# PCB_dol.net
KiCad netlist of a schematic drawn in EAGLE
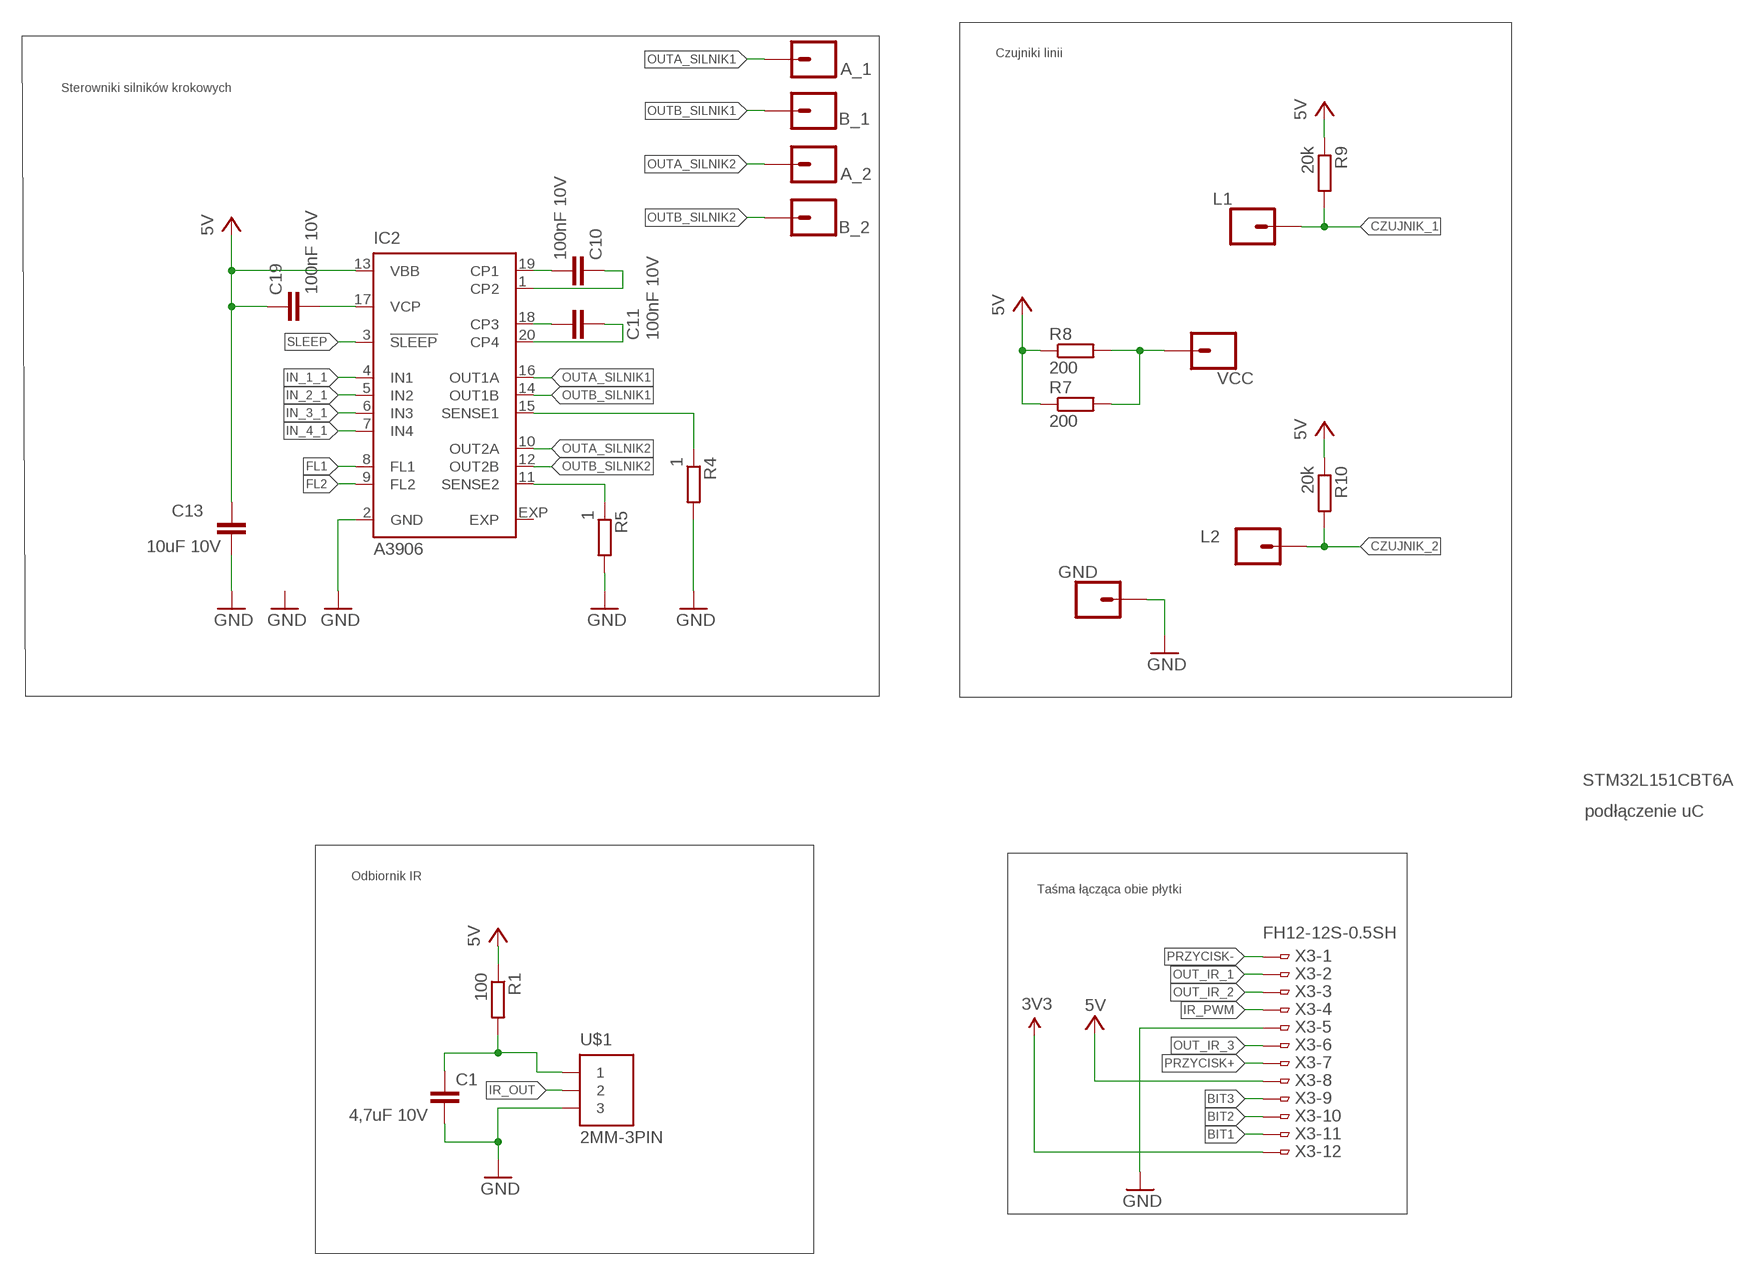
[diagram p0: schematic, sheet 1, part 1 of 2]
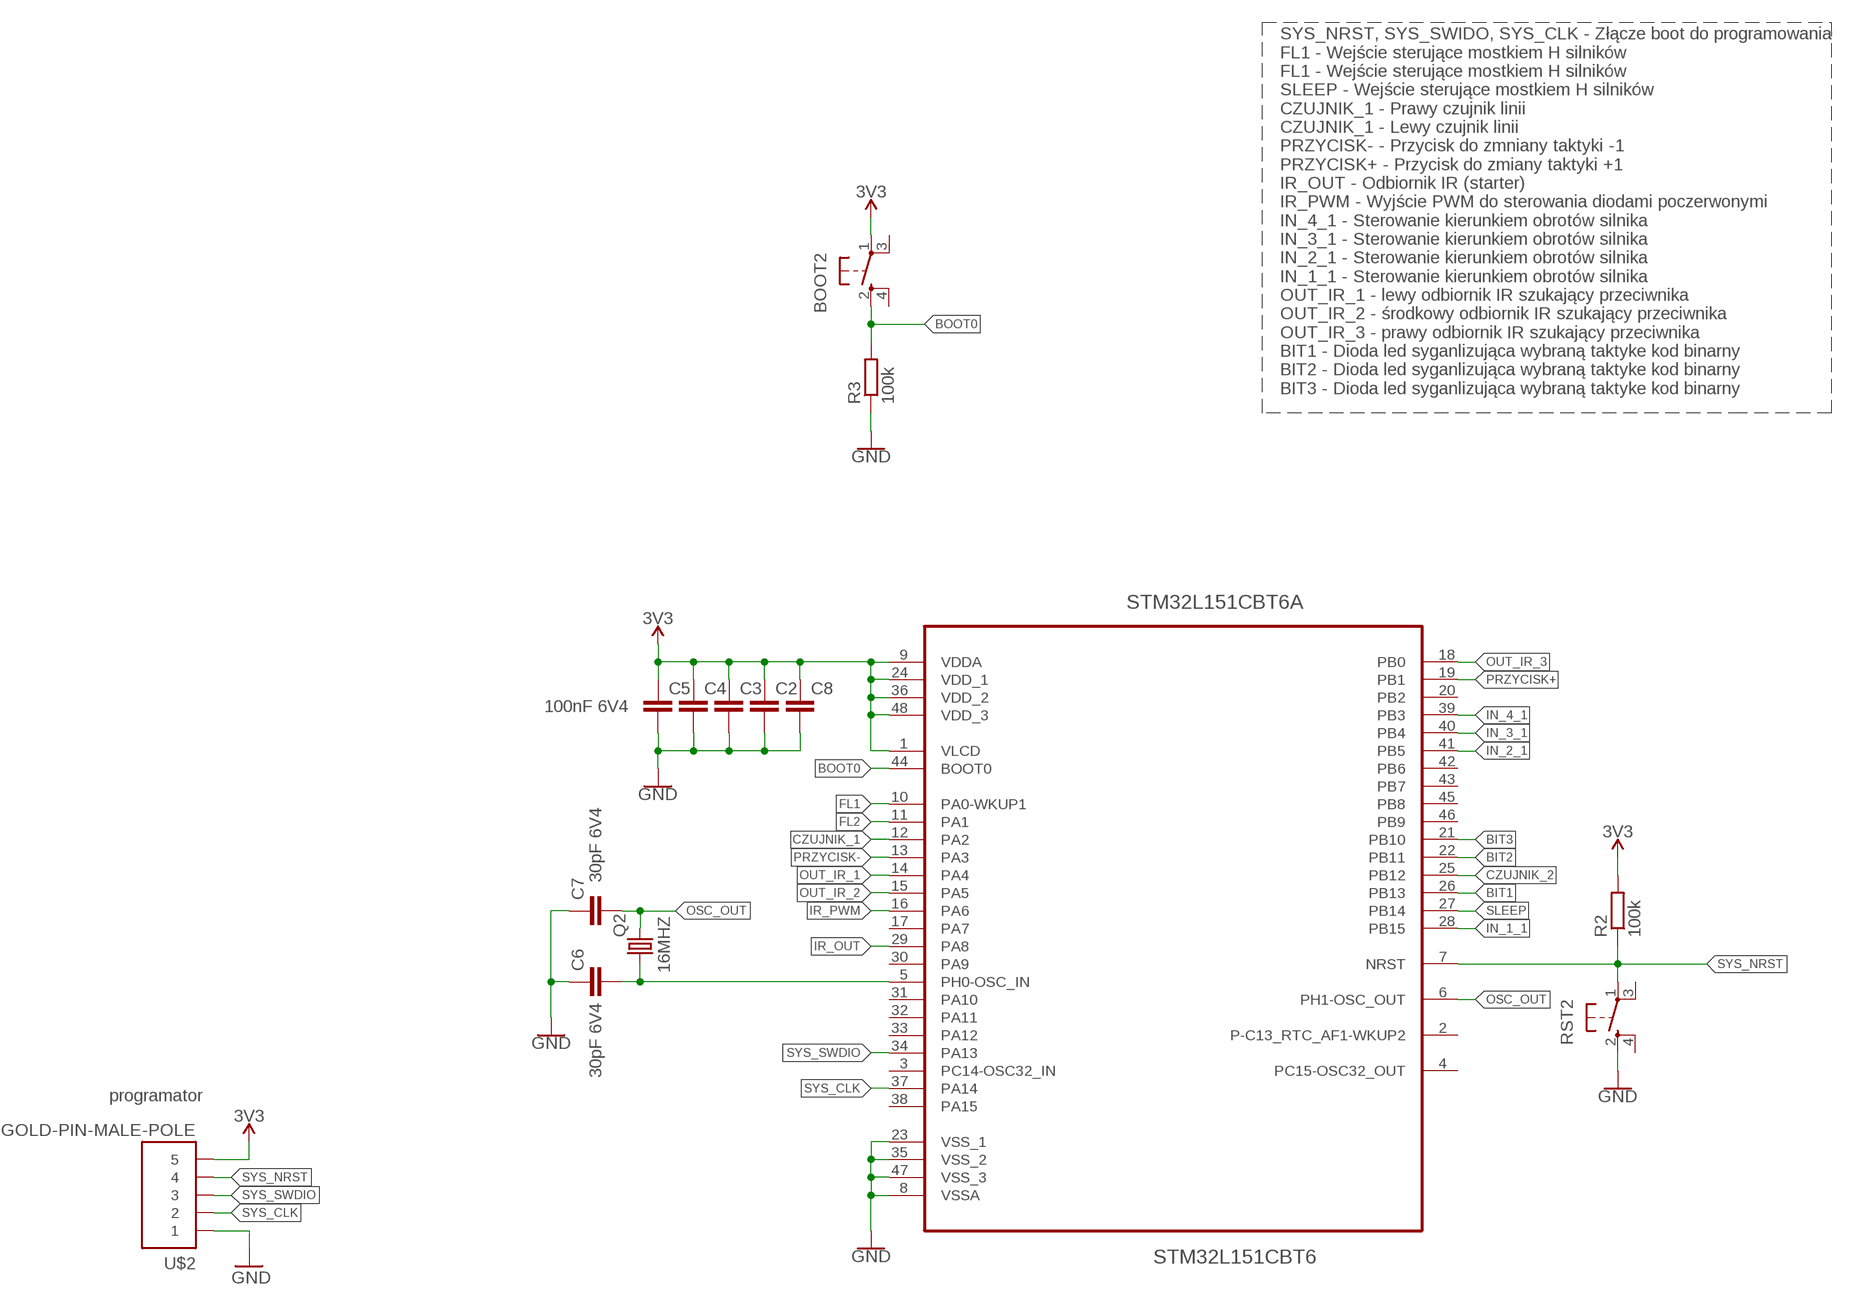
[diagram p1: schematic, sheet 1, part 2 of 2]

(export (version "E")
  (design (tool "Eeschema 10.0.6"))
  (components
    (comp (ref "A_1")
      (value "CONN_01PTH_NO_SILK_KIT")
      (footprint "eagle-import:1X01NS_KIT")
      (libsource (lib "eagle-import") (part "CONN_01PTH_NO_SILK_KIT"))
    )
    (comp (ref "A_2")
      (value "CONN_01PTH_NO_SILK_KIT")
      (footprint "eagle-import:1X01NS_KIT")
      (libsource (lib "eagle-import") (part "CONN_01PTH_NO_SILK_KIT"))
    )
    (comp (ref "BOOT2")
      (value "SPST_TACT-KMR2")
      (footprint "eagle-import:KMR2")
      (libsource (lib "eagle-import") (part "SPST_TACT-KMR2"))
    )
    (comp (ref "B_1")
      (value "CONN_01PTH_NO_SILK_KIT")
      (footprint "eagle-import:1X01NS_KIT")
      (libsource (lib "eagle-import") (part "CONN_01PTH_NO_SILK_KIT"))
    )
    (comp (ref "B_2")
      (value "CONN_01PTH_NO_SILK_KIT")
      (footprint "eagle-import:1X01NS_KIT")
      (libsource (lib "eagle-import") (part "CONN_01PTH_NO_SILK_KIT"))
    )
    (comp (ref "C1")
      (value "4,7uF 10V")
      (footprint "eagle-import:C0402")
      (libsource (lib "eagle-import") (part "C-EUC0402"))
    )
    (comp (ref "C2")
      (value "100nF 6V4")
      (footprint "eagle-import:C0402")
      (libsource (lib "eagle-import") (part "C-EUC0402"))
    )
    (comp (ref "C3")
      (value "100nF 6V4")
      (footprint "eagle-import:C0402")
      (libsource (lib "eagle-import") (part "C-EUC0402"))
    )
    (comp (ref "C4")
      (value "100nF 6V4")
      (footprint "eagle-import:C0402")
      (libsource (lib "eagle-import") (part "C-EUC0402"))
    )
    (comp (ref "C5")
      (value "100nF 6V4")
      (footprint "eagle-import:C0402")
      (libsource (lib "eagle-import") (part "C-EUC0402"))
    )
    (comp (ref "C6")
      (value "30pF 6V4")
      (footprint "eagle-import:C0402")
      (libsource (lib "eagle-import") (part "C-EUC0402"))
    )
    (comp (ref "C7")
      (value "30pF 6V4")
      (footprint "eagle-import:C0402")
      (libsource (lib "eagle-import") (part "C-EUC0402"))
    )
    (comp (ref "C8")
      (value "100nF 6V4")
      (footprint "eagle-import:C0402")
      (libsource (lib "eagle-import") (part "C-EUC0402"))
    )
    (comp (ref "C10")
      (value "100nF 10V")
      (footprint "eagle-import:C0402")
      (libsource (lib "eagle-import") (part "C-EUC0402"))
    )
    (comp (ref "C11")
      (value "100nF 10V")
      (footprint "eagle-import:C0402")
      (libsource (lib "eagle-import") (part "C-EUC0402"))
    )
    (comp (ref "C13")
      (value "10uF 10V")
      (footprint "eagle-import:C0402")
      (libsource (lib "eagle-import") (part "C-EUC0402"))
    )
    (comp (ref "C19")
      (value "100nF 10V")
      (footprint "eagle-import:C0402")
      (libsource (lib "eagle-import") (part "C-EUC0402"))
    )
    (comp (ref "GND")
      (value "CONN_01PTH_NO_SILK_KIT")
      (footprint "eagle-import:1X01NS_KIT")
      (libsource (lib "eagle-import") (part "CONN_01PTH_NO_SILK_KIT"))
    )
    (comp (ref "IC2")
      (value "A3906")
      (footprint "eagle-import:QFN20")
      (libsource (lib "eagle-import") (part "A3906"))
    )
    (comp (ref "L1")
      (value "CONN_01PTH_NO_SILK_KIT")
      (footprint "eagle-import:1X01NS_KIT")
      (libsource (lib "eagle-import") (part "CONN_01PTH_NO_SILK_KIT"))
    )
    (comp (ref "L2")
      (value "CONN_01PTH_NO_SILK_KIT")
      (footprint "eagle-import:1X01NS_KIT")
      (libsource (lib "eagle-import") (part "CONN_01PTH_NO_SILK_KIT"))
    )
    (comp (ref "Q2")
      (value "16MHZ")
      (footprint "eagle-import:3.2X2.5_KX-7")
      (libsource (lib "eagle-import") (part "KX-7"))
    )
    (comp (ref "R1")
      (value "100")
      (footprint "eagle-import:R0402")
      (libsource (lib "eagle-import") (part "R-EU_R0402"))
    )
    (comp (ref "R2")
      (value "100k")
      (footprint "eagle-import:R0402")
      (libsource (lib "eagle-import") (part "R-EU_R0402"))
    )
    (comp (ref "R3")
      (value "100k")
      (footprint "eagle-import:R0402")
      (libsource (lib "eagle-import") (part "R-EU_R0402"))
    )
    (comp (ref "R4")
      (value "1")
      (footprint "eagle-import:R0402")
      (libsource (lib "eagle-import") (part "R-EU_R0402"))
    )
    (comp (ref "R5")
      (value "1")
      (footprint "eagle-import:R0402")
      (libsource (lib "eagle-import") (part "R-EU_R0402"))
    )
    (comp (ref "R7")
      (value "200")
      (footprint "eagle-import:R0805")
      (libsource (lib "eagle-import") (part "R-EU_R0805"))
    )
    (comp (ref "R8")
      (value "200")
      (footprint "eagle-import:R0805")
      (libsource (lib "eagle-import") (part "R-EU_R0805"))
    )
    (comp (ref "R9")
      (value "20k")
      (footprint "eagle-import:R0402")
      (libsource (lib "eagle-import") (part "R-EU_R0402"))
    )
    (comp (ref "R10")
      (value "20k")
      (footprint "eagle-import:R0402")
      (libsource (lib "eagle-import") (part "R-EU_R0402"))
    )
    (comp (ref "RST2")
      (value "SPST_TACT-KMR2")
      (footprint "eagle-import:KMR2")
      (libsource (lib "eagle-import") (part "SPST_TACT-KMR2"))
    )
    (comp (ref "STM32L151CBT6A")
      (value "STM32L151CBT6")
      (footprint "eagle-import:QFP50P900X900X160-48N")
      (libsource (lib "eagle-import") (part "STM32L151CBT6"))
    )
    (comp (ref "U$1")
      (value "2MM-3PIN")
      (footprint "eagle-import:2MM-3PIN")
      (libsource (lib "eagle-import") (part "2MM-3PIN"))
    )
    (comp (ref "U$2")
      (value "GOLD-PIN-MALE-POLE")
      (footprint "eagle-import:PIN5")
      (libsource (lib "eagle-import") (part "GOLD-PIN-MALE-POLE"))
    )
    (comp (ref "VCC")
      (value "CONN_01PTH_NO_SILK_KIT")
      (footprint "eagle-import:1X01NS_KIT")
      (libsource (lib "eagle-import") (part "CONN_01PTH_NO_SILK_KIT"))
    )
    (comp (ref "X3")
      (value "FH12-12S-0.5SH")
      (footprint "eagle-import:FH12-12S-0.5SH")
      (fields (field (name "MPN") "FH12-12S-0.5SH(55)"))
      (libsource (lib "eagle-import") (part "FH12-12S-0.5SH"))
    )
  )
  (nets
    (net (code "1") (name "3V3") (class "Default")
      (node (ref "BOOT2") (pin "1") (pinfunction "P_1") (pintype "passive"))
      (node (ref "C2") (pin "1") (pinfunction "1_1") (pintype "passive"))
      (node (ref "C3") (pin "1") (pinfunction "1_1") (pintype "passive"))
      (node (ref "C4") (pin "1") (pinfunction "1_1") (pintype "passive"))
      (node (ref "C5") (pin "1") (pinfunction "1_1") (pintype "passive"))
      (node (ref "C8") (pin "1") (pinfunction "1_1") (pintype "passive"))
      (node (ref "R2") (pin "2") (pinfunction "2_2") (pintype "passive"))
      (node (ref "STM32L151CBT6A") (pin "1") (pinfunction "VLCD_1") (pintype "power_in"))
      (node (ref "STM32L151CBT6A") (pin "24") (pinfunction "VDD_1_24") (pintype "power_in"))
      (node (ref "STM32L151CBT6A") (pin "36") (pinfunction "VDD_2_36") (pintype "power_in"))
      (node (ref "STM32L151CBT6A") (pin "48") (pinfunction "VDD_3_48") (pintype "power_in"))
      (node (ref "STM32L151CBT6A") (pin "9") (pinfunction "VDDA_9") (pintype "power_in"))
      (node (ref "U$2") (pin "P$5") (pinfunction "5_P$5") (pintype "input"))
      (node (ref "X3") (pin "12") (pinfunction "1_12") (pintype "passive"))
    )
    (net (code "2") (name "5V") (class "Default")
      (node (ref "C13") (pin "2") (pinfunction "2_2") (pintype "passive"))
      (node (ref "C19") (pin "2") (pinfunction "2_2") (pintype "passive"))
      (node (ref "IC2") (pin "13") (pinfunction "VBB_13") (pintype "power_in"))
      (node (ref "R1") (pin "1") (pinfunction "1_1") (pintype "passive"))
      (node (ref "R10") (pin "1") (pinfunction "1_1") (pintype "passive"))
      (node (ref "R7") (pin "1") (pinfunction "1_1") (pintype "passive"))
      (node (ref "R8") (pin "1") (pinfunction "1_1") (pintype "passive"))
      (node (ref "R9") (pin "1") (pinfunction "1_1") (pintype "passive"))
      (node (ref "X3") (pin "8") (pinfunction "1_8") (pintype "passive"))
    )
    (net (code "3") (name "BIT1") (class "Default")
      (node (ref "STM32L151CBT6A") (pin "26") (pinfunction "PB13_26") (pintype "bidirectional"))
      (node (ref "X3") (pin "11") (pinfunction "1_11") (pintype "passive"))
    )
    (net (code "4") (name "BIT2") (class "Default")
      (node (ref "STM32L151CBT6A") (pin "22") (pinfunction "PB11_22") (pintype "bidirectional"))
      (node (ref "X3") (pin "10") (pinfunction "1_10") (pintype "passive"))
    )
    (net (code "5") (name "BIT3") (class "Default")
      (node (ref "STM32L151CBT6A") (pin "21") (pinfunction "PB10_21") (pintype "bidirectional"))
      (node (ref "X3") (pin "9") (pinfunction "1_9") (pintype "passive"))
    )
    (net (code "6") (name "BOOT0") (class "Default")
      (node (ref "BOOT2") (pin "2") (pinfunction "S_2") (pintype "passive"))
      (node (ref "R3") (pin "2") (pinfunction "2_2") (pintype "passive"))
      (node (ref "STM32L151CBT6A") (pin "44") (pinfunction "BOOT0_44") (pintype "input"))
    )
    (net (code "7") (name "CZUJNIK_1") (class "Default")
      (node (ref "L1") (pin "1") (pinfunction "1_1") (pintype "passive"))
      (node (ref "R9") (pin "2") (pinfunction "2_2") (pintype "passive"))
      (node (ref "STM32L151CBT6A") (pin "12") (pinfunction "PA2_12") (pintype "bidirectional"))
    )
    (net (code "8") (name "CZUJNIK_2") (class "Default")
      (node (ref "L2") (pin "1") (pinfunction "1_1") (pintype "passive"))
      (node (ref "R10") (pin "2") (pinfunction "2_2") (pintype "passive"))
      (node (ref "STM32L151CBT6A") (pin "25") (pinfunction "PB12_25") (pintype "bidirectional"))
    )
    (net (code "9") (name "FL1") (class "Default")
      (node (ref "IC2") (pin "8") (pinfunction "FL1_8") (pintype "input"))
      (node (ref "STM32L151CBT6A") (pin "10") (pinfunction "PA0-WKUP1_10") (pintype "bidirectional"))
    )
    (net (code "10") (name "FL2") (class "Default")
      (node (ref "IC2") (pin "9") (pinfunction "FL2_9") (pintype "input"))
      (node (ref "STM32L151CBT6A") (pin "11") (pinfunction "PA1_11") (pintype "bidirectional"))
    )
    (net (code "11") (name "GND") (class "Default")
      (node (ref "C1") (pin "2") (pinfunction "2_2") (pintype "passive"))
      (node (ref "C13") (pin "1") (pinfunction "1_1") (pintype "passive"))
      (node (ref "C2") (pin "2") (pinfunction "2_2") (pintype "passive"))
      (node (ref "C3") (pin "2") (pinfunction "2_2") (pintype "passive"))
      (node (ref "C4") (pin "2") (pinfunction "2_2") (pintype "passive"))
      (node (ref "C5") (pin "2") (pinfunction "2_2") (pintype "passive"))
      (node (ref "C6") (pin "1") (pinfunction "1_1") (pintype "passive"))
      (node (ref "C7") (pin "1") (pinfunction "1_1") (pintype "passive"))
      (node (ref "C8") (pin "2") (pinfunction "2_2") (pintype "passive"))
      (node (ref "GND") (pin "1") (pinfunction "1_1") (pintype "passive"))
      (node (ref "IC2") (pin "2") (pinfunction "GND_2") (pintype "power_in"))
      (node (ref "R3") (pin "1") (pinfunction "1_1") (pintype "passive"))
      (node (ref "R4") (pin "2") (pinfunction "2_2") (pintype "passive"))
      (node (ref "R5") (pin "2") (pinfunction "2_2") (pintype "passive"))
      (node (ref "RST2") (pin "2") (pinfunction "S_2") (pintype "passive"))
      (node (ref "STM32L151CBT6A") (pin "23") (pinfunction "VSS_1_23") (pintype "power_in"))
      (node (ref "STM32L151CBT6A") (pin "35") (pinfunction "VSS_2_35") (pintype "power_in"))
      (node (ref "STM32L151CBT6A") (pin "47") (pinfunction "VSS_3_47") (pintype "power_in"))
      (node (ref "STM32L151CBT6A") (pin "8") (pinfunction "VSSA_8") (pintype "power_in"))
      (node (ref "U$1") (pin "P$3") (pinfunction "3_P$3") (pintype "input"))
      (node (ref "U$2") (pin "P$1") (pinfunction "1_P$1") (pintype "input"))
      (node (ref "X3") (pin "5") (pinfunction "1_5") (pintype "passive"))
    )
    (net (code "12") (name "IN_1_1") (class "Default")
      (node (ref "IC2") (pin "4") (pinfunction "IN1_4") (pintype "input"))
      (node (ref "STM32L151CBT6A") (pin "28") (pinfunction "PB15_28") (pintype "bidirectional"))
    )
    (net (code "13") (name "IN_2_1") (class "Default")
      (node (ref "IC2") (pin "5") (pinfunction "IN2_5") (pintype "input"))
      (node (ref "STM32L151CBT6A") (pin "41") (pinfunction "PB5_41") (pintype "bidirectional"))
    )
    (net (code "14") (name "IN_3_1") (class "Default")
      (node (ref "IC2") (pin "6") (pinfunction "IN3_6") (pintype "input"))
      (node (ref "STM32L151CBT6A") (pin "40") (pinfunction "PB4_40") (pintype "bidirectional"))
    )
    (net (code "15") (name "IN_4_1") (class "Default")
      (node (ref "IC2") (pin "7") (pinfunction "IN4_7") (pintype "input"))
      (node (ref "STM32L151CBT6A") (pin "39") (pinfunction "PB3_39") (pintype "bidirectional"))
    )
    (net (code "16") (name "IR_OUT") (class "Default")
      (node (ref "STM32L151CBT6A") (pin "29") (pinfunction "PA8_29") (pintype "bidirectional"))
      (node (ref "U$1") (pin "P$2") (pinfunction "2_P$2") (pintype "input"))
    )
    (net (code "17") (name "IR_PWM") (class "Default")
      (node (ref "STM32L151CBT6A") (pin "16") (pinfunction "PA6_16") (pintype "bidirectional"))
      (node (ref "X3") (pin "4") (pinfunction "1_4") (pintype "passive"))
    )
    (net (code "18") (name "Net-(IC2-CP1)") (class "Default")
      (node (ref "C10") (pin "1") (pinfunction "1_1") (pintype "passive"))
      (node (ref "IC2") (pin "19") (pinfunction "CP1_19") (pintype "passive"))
    )
    (net (code "19") (name "Net-(IC2-CP2)") (class "Default")
      (node (ref "C10") (pin "2") (pinfunction "2_2") (pintype "passive"))
      (node (ref "IC2") (pin "1") (pinfunction "CP2_1") (pintype "passive"))
    )
    (net (code "20") (name "Net-(IC2-CP3)") (class "Default")
      (node (ref "C11") (pin "1") (pinfunction "1_1") (pintype "passive"))
      (node (ref "IC2") (pin "18") (pinfunction "CP3_18") (pintype "passive"))
    )
    (net (code "21") (name "Net-(IC2-CP4)") (class "Default")
      (node (ref "C11") (pin "2") (pinfunction "2_2") (pintype "passive"))
      (node (ref "IC2") (pin "20") (pinfunction "CP4_20") (pintype "passive"))
    )
    (net (code "22") (name "Net-(IC2-SENSE1)") (class "Default")
      (node (ref "IC2") (pin "15") (pinfunction "SENSE1_15") (pintype "input"))
      (node (ref "R4") (pin "1") (pinfunction "1_1") (pintype "passive"))
    )
    (net (code "23") (name "Net-(IC2-SENSE2)") (class "Default")
      (node (ref "IC2") (pin "11") (pinfunction "SENSE2_11") (pintype "input"))
      (node (ref "R5") (pin "1") (pinfunction "1_1") (pintype "passive"))
    )
    (net (code "24") (name "Net-(IC2-VCP)") (class "Default")
      (node (ref "C19") (pin "1") (pinfunction "1_1") (pintype "passive"))
      (node (ref "IC2") (pin "17") (pinfunction "VCP_17") (pintype "passive"))
    )
    (net (code "25") (name "Net-(R7-Pad2)") (class "Default")
      (node (ref "R7") (pin "2") (pinfunction "2_2") (pintype "passive"))
      (node (ref "R8") (pin "2") (pinfunction "2_2") (pintype "passive"))
      (node (ref "VCC") (pin "1") (pinfunction "1_1") (pintype "passive"))
    )
    (net (code "26") (name "Net-(STM32L151CBT6A-PH0-OSC_IN)") (class "Default")
      (node (ref "C6") (pin "2") (pinfunction "2_2") (pintype "passive"))
      (node (ref "Q2") (pin "1") (pinfunction "1_1") (pintype "passive"))
      (node (ref "STM32L151CBT6A") (pin "5") (pinfunction "PH0-OSC_IN_5") (pintype "input"))
    )
    (net (code "27") (name "Net-(U$1-1)") (class "Default")
      (node (ref "C1") (pin "1") (pinfunction "1_1") (pintype "passive"))
      (node (ref "R1") (pin "2") (pinfunction "2_2") (pintype "passive"))
      (node (ref "U$1") (pin "P$1") (pinfunction "1_P$1") (pintype "input"))
    )
    (net (code "28") (name "OSC_OUT") (class "Default")
      (node (ref "C7") (pin "2") (pinfunction "2_2") (pintype "passive"))
      (node (ref "Q2") (pin "3") (pinfunction "2_3") (pintype "passive"))
      (node (ref "STM32L151CBT6A") (pin "6") (pinfunction "PH1-OSC_OUT_6") (pintype "output"))
    )
    (net (code "29") (name "OUTA_SILNIK1") (class "Default")
      (node (ref "A_1") (pin "1") (pinfunction "1_1") (pintype "passive"))
      (node (ref "IC2") (pin "16") (pinfunction "OUT1A_16") (pintype "output"))
    )
    (net (code "30") (name "OUTA_SILNIK2") (class "Default")
      (node (ref "A_2") (pin "1") (pinfunction "1_1") (pintype "passive"))
      (node (ref "IC2") (pin "10") (pinfunction "OUT2A_10") (pintype "output"))
    )
    (net (code "31") (name "OUTB_SILNIK1") (class "Default")
      (node (ref "B_1") (pin "1") (pinfunction "1_1") (pintype "passive"))
      (node (ref "IC2") (pin "14") (pinfunction "OUT1B_14") (pintype "output"))
    )
    (net (code "32") (name "OUTB_SILNIK2") (class "Default")
      (node (ref "B_2") (pin "1") (pinfunction "1_1") (pintype "passive"))
      (node (ref "IC2") (pin "12") (pinfunction "OUT2B_12") (pintype "output"))
    )
    (net (code "33") (name "OUT_IR_1") (class "Default")
      (node (ref "STM32L151CBT6A") (pin "14") (pinfunction "PA4_14") (pintype "bidirectional"))
      (node (ref "X3") (pin "2") (pinfunction "1_2") (pintype "passive"))
    )
    (net (code "34") (name "OUT_IR_2") (class "Default")
      (node (ref "STM32L151CBT6A") (pin "15") (pinfunction "PA5_15") (pintype "bidirectional"))
      (node (ref "X3") (pin "3") (pinfunction "1_3") (pintype "passive"))
    )
    (net (code "35") (name "OUT_IR_3") (class "Default")
      (node (ref "STM32L151CBT6A") (pin "18") (pinfunction "PB0_18") (pintype "bidirectional"))
      (node (ref "X3") (pin "6") (pinfunction "1_6") (pintype "passive"))
    )
    (net (code "36") (name "PRZYCISK+") (class "Default")
      (node (ref "STM32L151CBT6A") (pin "19") (pinfunction "PB1_19") (pintype "bidirectional"))
      (node (ref "X3") (pin "7") (pinfunction "1_7") (pintype "passive"))
    )
    (net (code "37") (name "PRZYCISK-") (class "Default")
      (node (ref "STM32L151CBT6A") (pin "13") (pinfunction "PA3_13") (pintype "bidirectional"))
      (node (ref "X3") (pin "1") (pinfunction "1_1") (pintype "passive"))
    )
    (net (code "38") (name "SLEEP") (class "Default")
      (node (ref "IC2") (pin "3") (pinfunction "~{SLEEP}_3") (pintype "input"))
      (node (ref "STM32L151CBT6A") (pin "27") (pinfunction "PB14_27") (pintype "bidirectional"))
    )
    (net (code "39") (name "SYS_CLK") (class "Default")
      (node (ref "STM32L151CBT6A") (pin "37") (pinfunction "PA14_37") (pintype "bidirectional"))
      (node (ref "U$2") (pin "P$2") (pinfunction "2_P$2") (pintype "input"))
    )
    (net (code "40") (name "SYS_NRST") (class "Default")
      (node (ref "R2") (pin "1") (pinfunction "1_1") (pintype "passive"))
      (node (ref "RST2") (pin "1") (pinfunction "P_1") (pintype "passive"))
      (node (ref "STM32L151CBT6A") (pin "7") (pinfunction "NRST_7") (pintype "bidirectional"))
      (node (ref "U$2") (pin "P$4") (pinfunction "4_P$4") (pintype "input"))
    )
    (net (code "41") (name "SYS_SWDIO") (class "Default")
      (node (ref "STM32L151CBT6A") (pin "34") (pinfunction "PA13_34") (pintype "bidirectional"))
      (node (ref "U$2") (pin "P$3") (pinfunction "3_P$3") (pintype "input"))
    )
    (net (code "42") (name "unconnected-(BOOT2-P1-Pad3)") (class "Default")
      (node (ref "BOOT2") (pin "3") (pinfunction "P1_3") (pintype "passive"))
    )
    (net (code "43") (name "unconnected-(BOOT2-S1-Pad4)") (class "Default")
      (node (ref "BOOT2") (pin "4") (pinfunction "S1_4") (pintype "passive"))
    )
    (net (code "44") (name "unconnected-(IC2-PadEXP)") (class "Default")
      (node (ref "IC2") (pin "EXP") (pinfunction "EXP_EXP") (pintype "passive"))
    )
    (net (code "45") (name "unconnected-(RST2-P1-Pad3)") (class "Default")
      (node (ref "RST2") (pin "3") (pinfunction "P1_3") (pintype "passive"))
    )
    (net (code "46") (name "unconnected-(RST2-S1-Pad4)") (class "Default")
      (node (ref "RST2") (pin "4") (pinfunction "S1_4") (pintype "passive"))
    )
    (net (code "47") (name "unconnected-(STM32L151CBT6A-P-C13_RTC_AF1-WKUP2-Pad2)") (class "Default")
      (node (ref "STM32L151CBT6A") (pin "2") (pinfunction "P-C13_RTC_AF1-WKUP2_2") (pintype "bidirectional"))
    )
    (net (code "48") (name "unconnected-(STM32L151CBT6A-PA7-Pad17)") (class "Default")
      (node (ref "STM32L151CBT6A") (pin "17") (pinfunction "PA7_17") (pintype "bidirectional"))
    )
    (net (code "49") (name "unconnected-(STM32L151CBT6A-PA9-Pad30)") (class "Default")
      (node (ref "STM32L151CBT6A") (pin "30") (pinfunction "PA9_30") (pintype "bidirectional"))
    )
    (net (code "50") (name "unconnected-(STM32L151CBT6A-PA10-Pad31)") (class "Default")
      (node (ref "STM32L151CBT6A") (pin "31") (pinfunction "PA10_31") (pintype "bidirectional"))
    )
    (net (code "51") (name "unconnected-(STM32L151CBT6A-PA11-Pad32)") (class "Default")
      (node (ref "STM32L151CBT6A") (pin "32") (pinfunction "PA11_32") (pintype "bidirectional"))
    )
    (net (code "52") (name "unconnected-(STM32L151CBT6A-PA12-Pad33)") (class "Default")
      (node (ref "STM32L151CBT6A") (pin "33") (pinfunction "PA12_33") (pintype "bidirectional"))
    )
    (net (code "53") (name "unconnected-(STM32L151CBT6A-PA15-Pad38)") (class "Default")
      (node (ref "STM32L151CBT6A") (pin "38") (pinfunction "PA15_38") (pintype "bidirectional"))
    )
    (net (code "54") (name "unconnected-(STM32L151CBT6A-PB2-Pad20)") (class "Default")
      (node (ref "STM32L151CBT6A") (pin "20") (pinfunction "PB2_20") (pintype "bidirectional"))
    )
    (net (code "55") (name "unconnected-(STM32L151CBT6A-PB6-Pad42)") (class "Default")
      (node (ref "STM32L151CBT6A") (pin "42") (pinfunction "PB6_42") (pintype "bidirectional"))
    )
    (net (code "56") (name "unconnected-(STM32L151CBT6A-PB7-Pad43)") (class "Default")
      (node (ref "STM32L151CBT6A") (pin "43") (pinfunction "PB7_43") (pintype "bidirectional"))
    )
    (net (code "57") (name "unconnected-(STM32L151CBT6A-PB8-Pad45)") (class "Default")
      (node (ref "STM32L151CBT6A") (pin "45") (pinfunction "PB8_45") (pintype "bidirectional"))
    )
    (net (code "58") (name "unconnected-(STM32L151CBT6A-PB9-Pad46)") (class "Default")
      (node (ref "STM32L151CBT6A") (pin "46") (pinfunction "PB9_46") (pintype "bidirectional"))
    )
    (net (code "59") (name "unconnected-(STM32L151CBT6A-PC14-OSC32_IN-Pad3)") (class "Default")
      (node (ref "STM32L151CBT6A") (pin "3") (pinfunction "PC14-OSC32_IN_3") (pintype "input"))
    )
    (net (code "60") (name "unconnected-(STM32L151CBT6A-PC15-OSC32_OUT-Pad4)") (class "Default")
      (node (ref "STM32L151CBT6A") (pin "4") (pinfunction "PC15-OSC32_OUT_4") (pintype "output"))
    )
  )
)
